# Fingerprint_lock.net
KiCad netlist of a schematic drawn in EAGLE
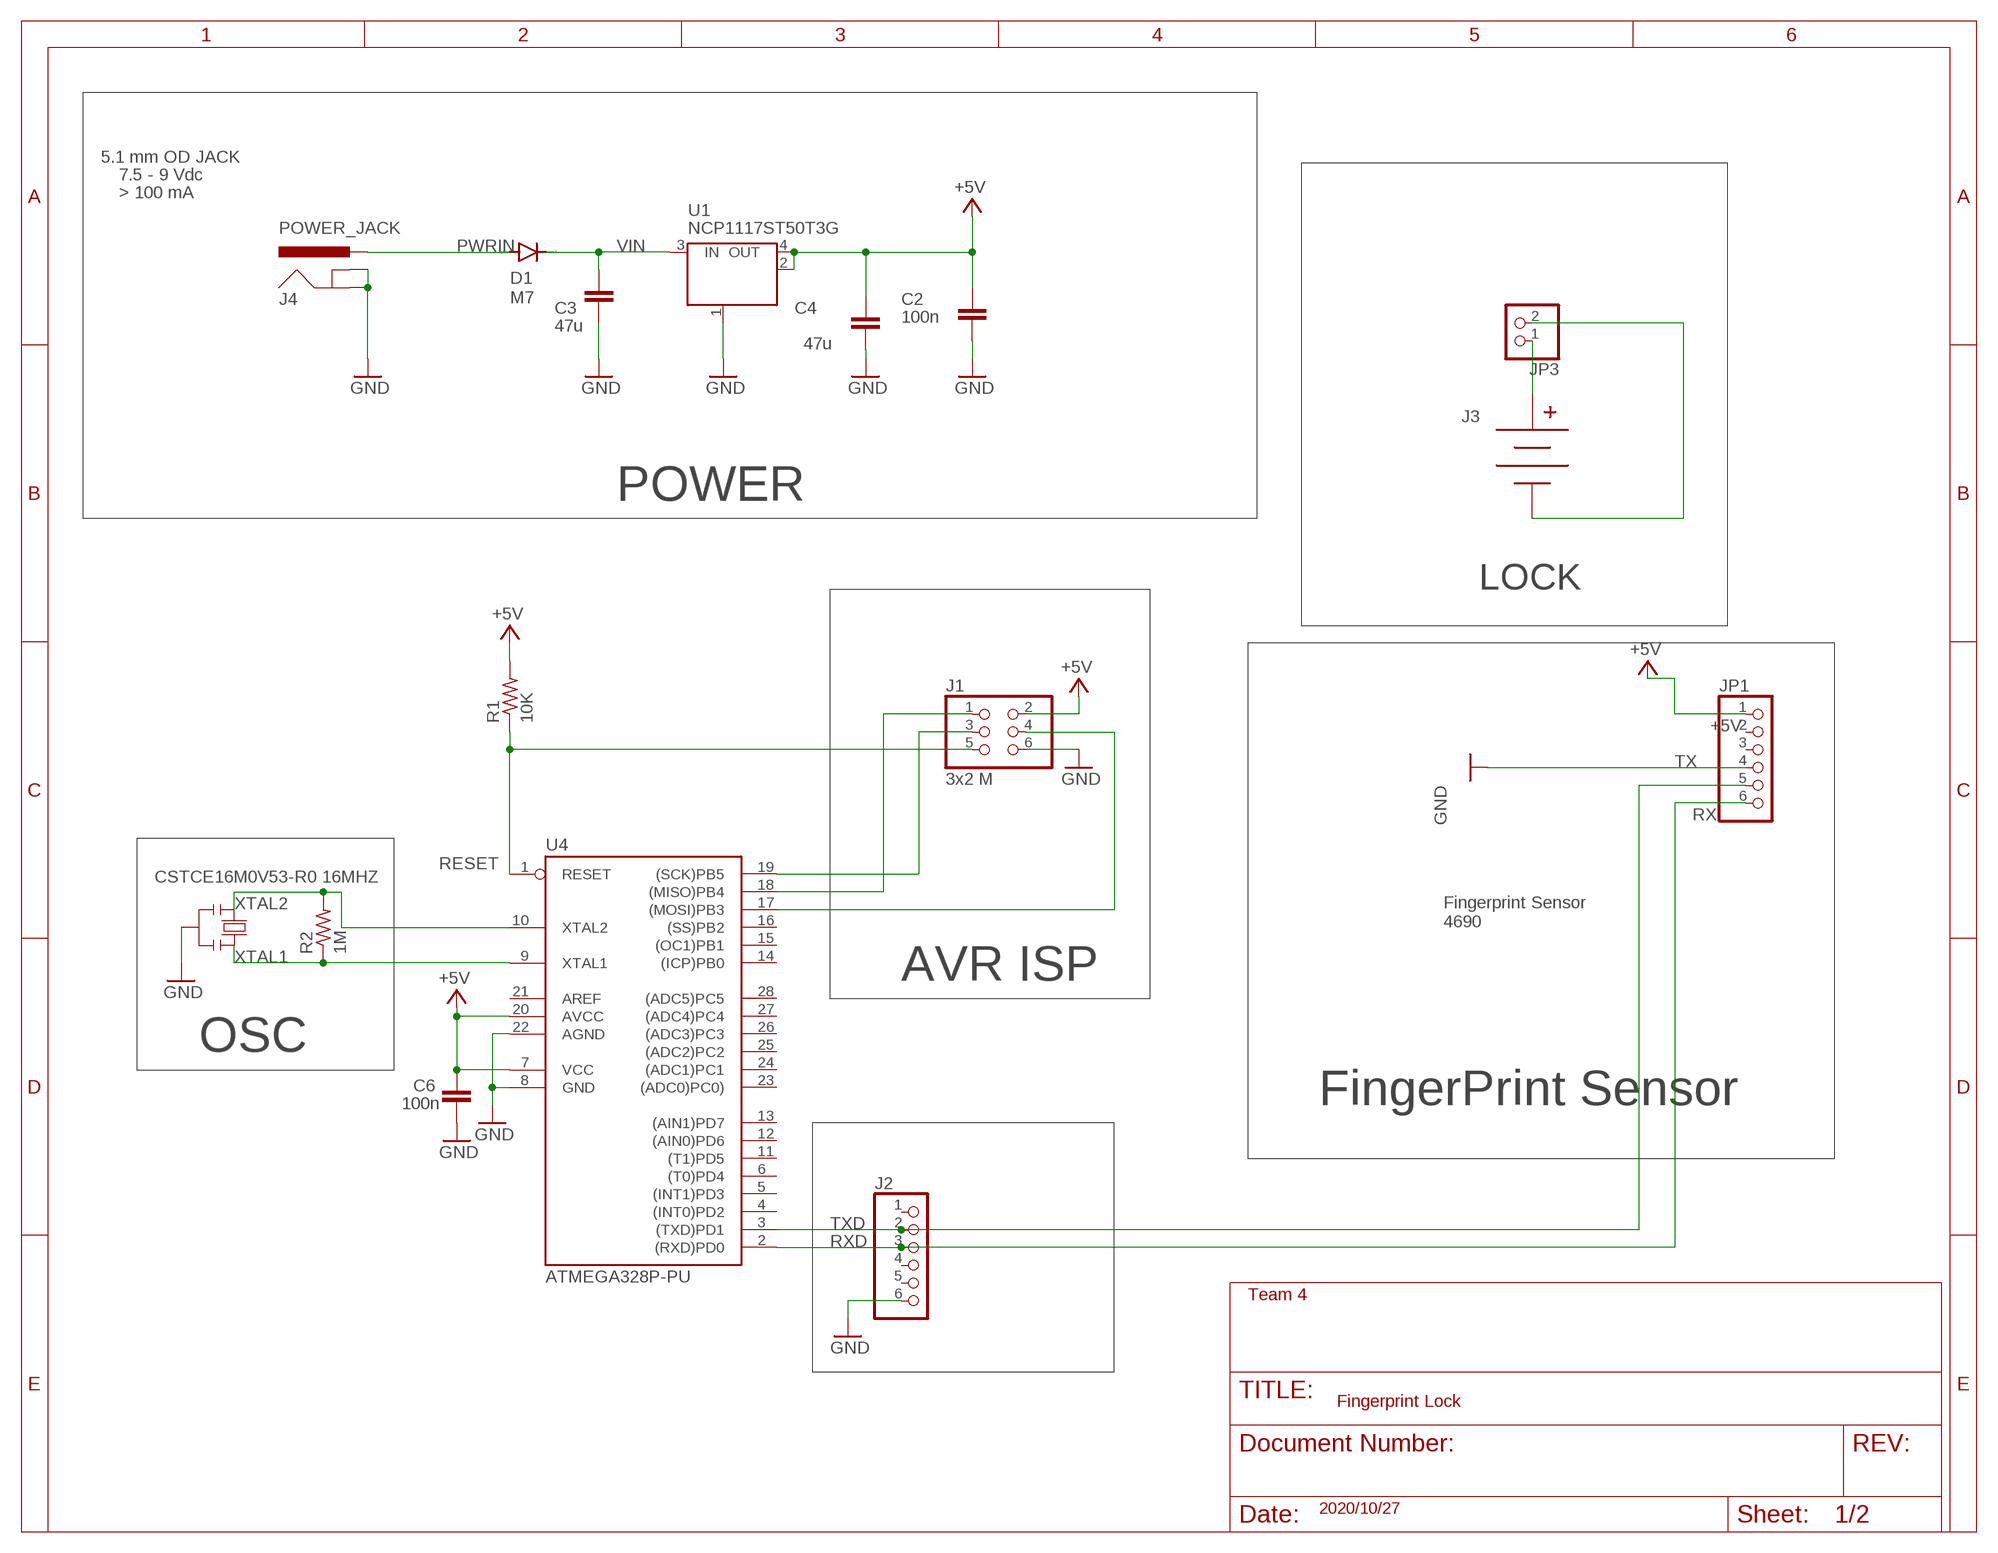
[diagram p0: schematic, sheet 1]

(export (version "E")
  (design (tool "Eeschema 10.0.6"))
  (components
    (comp (ref "C2")
      (value "100n")
      (footprint "eagle-import:C0805")
      (libsource (lib "eagle-import") (part "C-EUC0805"))
    )
    (comp (ref "C3")
      (value "47u")
      (footprint "eagle-import:C0805")
      (libsource (lib "eagle-import") (part "C-EUC0805"))
    )
    (comp (ref "C4")
      (value "47u")
      (footprint "eagle-import:C0805")
      (libsource (lib "eagle-import") (part "C-EUC0805"))
    )
    (comp (ref "C6")
      (value "100n")
      (footprint "eagle-import:C0805")
      (libsource (lib "eagle-import") (part "C-EUC0805"))
    )
    (comp (ref "D1")
      (value "M7")
      (footprint "eagle-import:SMB")
      (libsource (lib "eagle-import") (part "DIODE-SMB"))
    )
    (comp (ref "J1")
      (value "3x2 M")
      (footprint "eagle-import:2X03")
      (libsource (lib "eagle-import") (part "PINHD-2X3"))
    )
    (comp (ref "J2")
      (value "PINHD-1X6")
      (footprint "eagle-import:1X06")
      (libsource (lib "eagle-import") (part "pinhead_325_PINHD-1X6"))
    )
    (comp (ref "J3")
      (value "BC9VPC")
      (footprint "eagle-import:BC9VPC")
      (libsource (lib "eagle-import") (part "BC9VPC"))
    )
    (comp (ref "J4")
      (value "POWER_JACK")
      (footprint "eagle-import:POWER_JACK_PTH")
      (libsource (lib "eagle-import") (part "POWER_JACK"))
    )
    (comp (ref "JP1")
      (value "PINHD-1X6B")
      (footprint "eagle-import:1X06-BIG")
      (libsource (lib "eagle-import") (part "PINHD-1X6B"))
    )
    (comp (ref "JP3")
      (value "PINHD-1X2")
      (footprint "eagle-import:1X02")
      (libsource (lib "eagle-import") (part "PINHD-1X2"))
    )
    (comp (ref "R1")
      (value "10K")
      (footprint "eagle-import:R0805")
      (libsource (lib "eagle-import") (part "R-US_R0805"))
    )
    (comp (ref "R2")
      (value "1M")
      (footprint "eagle-import:R0805")
      (libsource (lib "eagle-import") (part "R-US_R0805"))
    )
    (comp (ref "U1")
      (value "NCP1117ST50T3G")
      (footprint "eagle-import:SOT223")
      (libsource (lib "eagle-import") (part "MC33269ST-3.3T3"))
    )
    (comp (ref "U4")
      (value "ATMEGA328P-PU")
      (footprint "eagle-import:DIL28-3")
      (libsource (lib "eagle-import") (part "ATMEGA328P-PU"))
    )
    (comp (ref "X1")
      (value "CSTCE16M0V53-R0 16MHZ")
      (footprint "eagle-import:RESONATOR")
      (libsource (lib "eagle-import") (part "RESONATORMU"))
    )
  )
  (nets
    (net (code "1") (name "+5V") (class "Default")
      (node (ref "C2") (pin "2") (pinfunction "2_2") (pintype "passive"))
      (node (ref "C4") (pin "2") (pinfunction "2_2") (pintype "passive"))
      (node (ref "C6") (pin "2") (pinfunction "2_2") (pintype "passive"))
      (node (ref "J1") (pin "2") (pinfunction "2_2") (pintype "passive"))
      (node (ref "JP1") (pin "1") (pinfunction "1_1") (pintype "passive"))
      (node (ref "R1") (pin "2") (pinfunction "2_2") (pintype "passive"))
      (node (ref "U1") (pin "2") (pinfunction "OUT_2") (pintype "passive"))
      (node (ref "U1") (pin "4") (pinfunction "OUT_4") (pintype "passive"))
      (node (ref "U4") (pin "20") (pinfunction "AVCC_20") (pintype "power_in"))
      (node (ref "U4") (pin "7") (pinfunction "VCC_7") (pintype "power_in"))
    )
    (net (code "2") (name "GND") (class "Default")
      (node (ref "C2") (pin "1") (pinfunction "1_1") (pintype "passive"))
      (node (ref "C3") (pin "1") (pinfunction "1_1") (pintype "passive"))
      (node (ref "C4") (pin "1") (pinfunction "1_1") (pintype "passive"))
      (node (ref "C6") (pin "1") (pinfunction "1_1") (pintype "passive"))
      (node (ref "J1") (pin "6") (pinfunction "6_6") (pintype "passive"))
      (node (ref "J2") (pin "6") (pinfunction "6_6") (pintype "passive"))
      (node (ref "J4") (pin "GND") (pinfunction "GND_GND") (pintype "bidirectional"))
      (node (ref "J4") (pin "GNDBREAK") (pinfunction "GNDBREAK_GNDBREAK") (pintype "bidirectional"))
      (node (ref "JP1") (pin "4") (pinfunction "4_4") (pintype "passive"))
      (node (ref "U1") (pin "1") (pinfunction "GND/ADJ_1") (pintype "input"))
      (node (ref "U4") (pin "22") (pinfunction "AGND_22") (pintype "power_in"))
      (node (ref "U4") (pin "8") (pinfunction "GND_8") (pintype "power_in"))
      (node (ref "X1") (pin "2") (pinfunction "2_2") (pintype "passive"))
    )
    (net (code "3") (name "Net-(J3-PadV+)") (class "Default")
      (node (ref "J3") (pin "V+") (pinfunction "V+_V+") (pintype "bidirectional"))
      (node (ref "JP3") (pin "1") (pinfunction "1_1") (pintype "passive"))
    )
    (net (code "4") (name "Net-(J3-PadV-)") (class "Default")
      (node (ref "J3") (pin "V-") (pinfunction "V-_V-") (pintype "bidirectional"))
      (node (ref "JP3") (pin "2") (pinfunction "2_2") (pintype "passive"))
    )
    (net (code "5") (name "Net-(U4-(MISO)PB4)") (class "Default")
      (node (ref "J1") (pin "1") (pinfunction "1_1") (pintype "passive"))
      (node (ref "U4") (pin "18") (pinfunction "(MISO)PB4_18") (pintype "bidirectional"))
    )
    (net (code "6") (name "Net-(U4-(MOSI)PB3)") (class "Default")
      (node (ref "J1") (pin "4") (pinfunction "4_4") (pintype "passive"))
      (node (ref "U4") (pin "17") (pinfunction "(MOSI)PB3_17") (pintype "bidirectional"))
    )
    (net (code "7") (name "Net-(U4-(SCK)PB5)") (class "Default")
      (node (ref "J1") (pin "3") (pinfunction "3_3") (pintype "passive"))
      (node (ref "U4") (pin "19") (pinfunction "(SCK)PB5_19") (pintype "bidirectional"))
    )
    (net (code "8") (name "PWRIN") (class "Default")
      (node (ref "D1") (pin "A") (pinfunction "A_A") (pintype "passive"))
      (node (ref "J4") (pin "PWR") (pinfunction "PWR_PWR") (pintype "bidirectional"))
    )
    (net (code "9") (name "RESET") (class "Default")
      (node (ref "J1") (pin "5") (pinfunction "5_5") (pintype "passive"))
      (node (ref "R1") (pin "1") (pinfunction "1_1") (pintype "passive"))
      (node (ref "U4") (pin "1") (pinfunction "RESET_1") (pintype "input"))
    )
    (net (code "10") (name "RXD") (class "Default")
      (node (ref "J2") (pin "3") (pinfunction "3_3") (pintype "passive"))
      (node (ref "JP1") (pin "6") (pinfunction "6_6") (pintype "passive"))
      (node (ref "U4") (pin "2") (pinfunction "(RXD)PD0_2") (pintype "bidirectional"))
    )
    (net (code "11") (name "TXD") (class "Default")
      (node (ref "J2") (pin "2") (pinfunction "2_2") (pintype "passive"))
      (node (ref "JP1") (pin "5") (pinfunction "5_5") (pintype "passive"))
      (node (ref "U4") (pin "3") (pinfunction "(TXD)PD1_3") (pintype "bidirectional"))
    )
    (net (code "12") (name "VIN") (class "Default")
      (node (ref "C3") (pin "2") (pinfunction "2_2") (pintype "passive"))
      (node (ref "D1") (pin "C") (pinfunction "C_C") (pintype "passive"))
      (node (ref "U1") (pin "3") (pinfunction "IN_3") (pintype "input"))
    )
    (net (code "13") (name "XTAL1") (class "Default")
      (node (ref "R2") (pin "1") (pinfunction "1_1") (pintype "passive"))
      (node (ref "U4") (pin "9") (pinfunction "XTAL1_9") (pintype "bidirectional"))
      (node (ref "X1") (pin "3") (pinfunction "3_3") (pintype "passive"))
    )
    (net (code "14") (name "XTAL2") (class "Default")
      (node (ref "R2") (pin "2") (pinfunction "2_2") (pintype "passive"))
      (node (ref "U4") (pin "10") (pinfunction "XTAL2_10") (pintype "bidirectional"))
      (node (ref "X1") (pin "1") (pinfunction "1_1") (pintype "passive"))
    )
    (net (code "15") (name "unconnected-(J2-Pad1)") (class "Default")
      (node (ref "J2") (pin "1") (pinfunction "1_1") (pintype "passive"))
    )
    (net (code "16") (name "unconnected-(J2-Pad4)") (class "Default")
      (node (ref "J2") (pin "4") (pinfunction "4_4") (pintype "passive"))
    )
    (net (code "17") (name "unconnected-(J2-Pad5)") (class "Default")
      (node (ref "J2") (pin "5") (pinfunction "5_5") (pintype "passive"))
    )
    (net (code "18") (name "unconnected-(JP1-Pad2)") (class "Default")
      (node (ref "JP1") (pin "2") (pinfunction "2_2") (pintype "passive"))
    )
    (net (code "19") (name "unconnected-(JP1-Pad3)") (class "Default")
      (node (ref "JP1") (pin "3") (pinfunction "3_3") (pintype "passive"))
    )
    (net (code "20") (name "unconnected-(U4-(ADC0)PC0)-Pad23)") (class "Default")
      (node (ref "U4") (pin "23") (pinfunction "(ADC0)PC0)_23") (pintype "bidirectional"))
    )
    (net (code "21") (name "unconnected-(U4-(ADC1)PC1-Pad24)") (class "Default")
      (node (ref "U4") (pin "24") (pinfunction "(ADC1)PC1_24") (pintype "bidirectional"))
    )
    (net (code "22") (name "unconnected-(U4-(ADC2)PC2-Pad25)") (class "Default")
      (node (ref "U4") (pin "25") (pinfunction "(ADC2)PC2_25") (pintype "bidirectional"))
    )
    (net (code "23") (name "unconnected-(U4-(ADC3)PC3-Pad26)") (class "Default")
      (node (ref "U4") (pin "26") (pinfunction "(ADC3)PC3_26") (pintype "bidirectional"))
    )
    (net (code "24") (name "unconnected-(U4-(ADC4)PC4-Pad27)") (class "Default")
      (node (ref "U4") (pin "27") (pinfunction "(ADC4)PC4_27") (pintype "bidirectional"))
    )
    (net (code "25") (name "unconnected-(U4-(ADC5)PC5-Pad28)") (class "Default")
      (node (ref "U4") (pin "28") (pinfunction "(ADC5)PC5_28") (pintype "bidirectional"))
    )
    (net (code "26") (name "unconnected-(U4-(AIN0)PD6-Pad12)") (class "Default")
      (node (ref "U4") (pin "12") (pinfunction "(AIN0)PD6_12") (pintype "bidirectional"))
    )
    (net (code "27") (name "unconnected-(U4-(AIN1)PD7-Pad13)") (class "Default")
      (node (ref "U4") (pin "13") (pinfunction "(AIN1)PD7_13") (pintype "bidirectional"))
    )
    (net (code "28") (name "unconnected-(U4-(ICP)PB0-Pad14)") (class "Default")
      (node (ref "U4") (pin "14") (pinfunction "(ICP)PB0_14") (pintype "bidirectional"))
    )
    (net (code "29") (name "unconnected-(U4-(INT0)PD2-Pad4)") (class "Default")
      (node (ref "U4") (pin "4") (pinfunction "(INT0)PD2_4") (pintype "bidirectional"))
    )
    (net (code "30") (name "unconnected-(U4-(INT1)PD3-Pad5)") (class "Default")
      (node (ref "U4") (pin "5") (pinfunction "(INT1)PD3_5") (pintype "bidirectional"))
    )
    (net (code "31") (name "unconnected-(U4-(OC1)PB1-Pad15)") (class "Default")
      (node (ref "U4") (pin "15") (pinfunction "(OC1)PB1_15") (pintype "bidirectional"))
    )
    (net (code "32") (name "unconnected-(U4-(SS)PB2-Pad16)") (class "Default")
      (node (ref "U4") (pin "16") (pinfunction "(SS)PB2_16") (pintype "bidirectional"))
    )
    (net (code "33") (name "unconnected-(U4-(T0)PD4-Pad6)") (class "Default")
      (node (ref "U4") (pin "6") (pinfunction "(T0)PD4_6") (pintype "bidirectional"))
    )
    (net (code "34") (name "unconnected-(U4-(T1)PD5-Pad11)") (class "Default")
      (node (ref "U4") (pin "11") (pinfunction "(T1)PD5_11") (pintype "bidirectional"))
    )
    (net (code "35") (name "unconnected-(U4-AREF-Pad21)") (class "Default")
      (node (ref "U4") (pin "21") (pinfunction "AREF_21") (pintype "passive"))
    )
  )
)
